# eyes.net
KiCad netlist of a schematic drawn in EAGLE
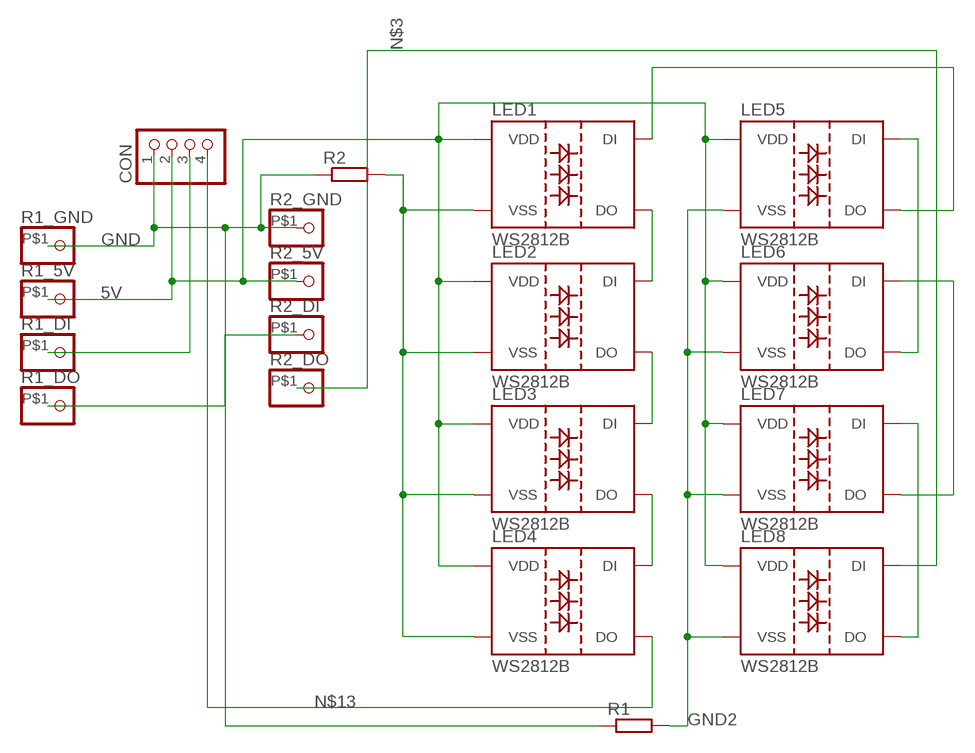
[diagram p0: schematic, sheet 1]

(export (version "E")
  (design (tool "Eeschema 10.0.6"))
  (components
    (comp (ref "CON")
      (value "PINHD-1X4")
      (footprint "eagle-import:1X04")
      (libsource (lib "eagle-import") (part "PINHD-1X4"))
    )
    (comp (ref "LED1")
      (value "WS2812B")
      (footprint "eagle-import:WS2812B")
      (libsource (lib "eagle-import") (part "WS2812B"))
    )
    (comp (ref "LED2")
      (value "WS2812B")
      (footprint "eagle-import:WS2812B")
      (libsource (lib "eagle-import") (part "WS2812B"))
    )
    (comp (ref "LED3")
      (value "WS2812B")
      (footprint "eagle-import:WS2812B")
      (libsource (lib "eagle-import") (part "WS2812B"))
    )
    (comp (ref "LED4")
      (value "WS2812B")
      (footprint "eagle-import:WS2812B")
      (libsource (lib "eagle-import") (part "WS2812B"))
    )
    (comp (ref "LED5")
      (value "WS2812B")
      (footprint "eagle-import:WS2812B")
      (libsource (lib "eagle-import") (part "WS2812B"))
    )
    (comp (ref "LED6")
      (value "WS2812B")
      (footprint "eagle-import:WS2812B")
      (libsource (lib "eagle-import") (part "WS2812B"))
    )
    (comp (ref "LED7")
      (value "WS2812B")
      (footprint "eagle-import:WS2812B")
      (libsource (lib "eagle-import") (part "WS2812B"))
    )
    (comp (ref "LED8")
      (value "WS2812B")
      (footprint "eagle-import:WS2812B")
      (libsource (lib "eagle-import") (part "WS2812B"))
    )
    (comp (ref "R1")
      (value "R-EU_0207/7")
      (footprint "eagle-import:0207_7")
      (libsource (lib "eagle-import") (part "R-EU_0207/7"))
    )
    (comp (ref "R1_5V")
      (value "PINHD-1X1-BIGPOGO")
      (footprint "eagle-import:1X1-BIGPOGO")
      (libsource (lib "eagle-import") (part "PINHD-1X1-BIGPOGO"))
    )
    (comp (ref "R1_DI")
      (value "PINHD-1X1-BIGPOGO")
      (footprint "eagle-import:1X1-BIGPOGO")
      (libsource (lib "eagle-import") (part "PINHD-1X1-BIGPOGO"))
    )
    (comp (ref "R1_DO")
      (value "PINHD-1X1-BIGPOGO")
      (footprint "eagle-import:1X1-BIGPOGO")
      (libsource (lib "eagle-import") (part "PINHD-1X1-BIGPOGO"))
    )
    (comp (ref "R1_GND")
      (value "PINHD-1X1-BIGPOGO")
      (footprint "eagle-import:1X1-BIGPOGO")
      (libsource (lib "eagle-import") (part "PINHD-1X1-BIGPOGO"))
    )
    (comp (ref "R2")
      (value "R-EU_0207/7")
      (footprint "eagle-import:0207_7")
      (libsource (lib "eagle-import") (part "R-EU_0207/7"))
    )
    (comp (ref "R2_5V")
      (value "PINHD-1X1-BIGPOGO")
      (footprint "eagle-import:1X1-BIGPOGO")
      (libsource (lib "eagle-import") (part "PINHD-1X1-BIGPOGO"))
    )
    (comp (ref "R2_DI")
      (value "PINHD-1X1-BIGPOGO")
      (footprint "eagle-import:1X1-BIGPOGO")
      (libsource (lib "eagle-import") (part "PINHD-1X1-BIGPOGO"))
    )
    (comp (ref "R2_DO")
      (value "PINHD-1X1-BIGPOGO")
      (footprint "eagle-import:1X1-BIGPOGO")
      (libsource (lib "eagle-import") (part "PINHD-1X1-BIGPOGO"))
    )
    (comp (ref "R2_GND")
      (value "PINHD-1X1-BIGPOGO")
      (footprint "eagle-import:1X1-BIGPOGO")
      (libsource (lib "eagle-import") (part "PINHD-1X1-BIGPOGO"))
    )
  )
  (nets
    (net (code "1") (name "/5V") (class "Default")
      (node (ref "CON") (pin "2") (pinfunction "2_2") (pintype "passive"))
      (node (ref "LED1") (pin "1") (pinfunction "VDD_1") (pintype "bidirectional"))
      (node (ref "LED2") (pin "1") (pinfunction "VDD_1") (pintype "bidirectional"))
      (node (ref "LED3") (pin "1") (pinfunction "VDD_1") (pintype "bidirectional"))
      (node (ref "LED4") (pin "1") (pinfunction "VDD_1") (pintype "bidirectional"))
      (node (ref "LED5") (pin "1") (pinfunction "VDD_1") (pintype "bidirectional"))
      (node (ref "LED6") (pin "1") (pinfunction "VDD_1") (pintype "bidirectional"))
      (node (ref "LED7") (pin "1") (pinfunction "VDD_1") (pintype "bidirectional"))
      (node (ref "LED8") (pin "1") (pinfunction "VDD_1") (pintype "bidirectional"))
      (node (ref "R1_5V") (pin "P$1") (pinfunction "1_P$1") (pintype "passive"))
      (node (ref "R2_5V") (pin "P$1") (pinfunction "1_P$1") (pintype "passive"))
    )
    (net (code "2") (name "/GND") (class "Default")
      (node (ref "CON") (pin "1") (pinfunction "1_1") (pintype "passive"))
      (node (ref "R1") (pin "1") (pinfunction "1_1") (pintype "passive"))
      (node (ref "R1_GND") (pin "P$1") (pinfunction "1_P$1") (pintype "passive"))
      (node (ref "R2") (pin "1") (pinfunction "1_1") (pintype "passive"))
      (node (ref "R2_GND") (pin "P$1") (pinfunction "1_P$1") (pintype "passive"))
    )
    (net (code "3") (name "/GND2") (class "Default")
      (node (ref "LED5") (pin "3") (pinfunction "VSS_3") (pintype "bidirectional"))
      (node (ref "LED6") (pin "3") (pinfunction "VSS_3") (pintype "bidirectional"))
      (node (ref "LED7") (pin "3") (pinfunction "VSS_3") (pintype "bidirectional"))
      (node (ref "LED8") (pin "3") (pinfunction "VSS_3") (pintype "bidirectional"))
      (node (ref "R1") (pin "2") (pinfunction "2_2") (pintype "passive"))
    )
    (net (code "4") (name "/N$3") (class "Default")
      (node (ref "LED8") (pin "4") (pinfunction "DI_4") (pintype "bidirectional"))
      (node (ref "R2_DO") (pin "P$1") (pinfunction "1_P$1") (pintype "passive"))
    )
    (net (code "5") (name "/N$13") (class "Default")
      (node (ref "CON") (pin "4") (pinfunction "4_4") (pintype "passive"))
      (node (ref "LED4") (pin "2") (pinfunction "DO_2") (pintype "bidirectional"))
    )
    (net (code "6") (name "Net-(LED1-DI)") (class "Default")
      (node (ref "LED1") (pin "4") (pinfunction "DI_4") (pintype "bidirectional"))
      (node (ref "LED5") (pin "2") (pinfunction "DO_2") (pintype "bidirectional"))
    )
    (net (code "7") (name "Net-(LED1-DO)") (class "Default")
      (node (ref "LED1") (pin "2") (pinfunction "DO_2") (pintype "bidirectional"))
      (node (ref "LED2") (pin "4") (pinfunction "DI_4") (pintype "bidirectional"))
    )
    (net (code "8") (name "Net-(LED1-VSS)") (class "Default")
      (node (ref "LED1") (pin "3") (pinfunction "VSS_3") (pintype "bidirectional"))
      (node (ref "LED2") (pin "3") (pinfunction "VSS_3") (pintype "bidirectional"))
      (node (ref "LED3") (pin "3") (pinfunction "VSS_3") (pintype "bidirectional"))
      (node (ref "LED4") (pin "3") (pinfunction "VSS_3") (pintype "bidirectional"))
      (node (ref "R2") (pin "2") (pinfunction "2_2") (pintype "passive"))
    )
    (net (code "9") (name "Net-(LED2-DO)") (class "Default")
      (node (ref "LED2") (pin "2") (pinfunction "DO_2") (pintype "bidirectional"))
      (node (ref "LED3") (pin "4") (pinfunction "DI_4") (pintype "bidirectional"))
    )
    (net (code "10") (name "Net-(LED3-DO)") (class "Default")
      (node (ref "LED3") (pin "2") (pinfunction "DO_2") (pintype "bidirectional"))
      (node (ref "LED4") (pin "4") (pinfunction "DI_4") (pintype "bidirectional"))
    )
    (net (code "11") (name "Net-(LED5-DI)") (class "Default")
      (node (ref "LED5") (pin "4") (pinfunction "DI_4") (pintype "bidirectional"))
      (node (ref "LED6") (pin "2") (pinfunction "DO_2") (pintype "bidirectional"))
    )
    (net (code "12") (name "Net-(LED6-DI)") (class "Default")
      (node (ref "LED6") (pin "4") (pinfunction "DI_4") (pintype "bidirectional"))
      (node (ref "LED7") (pin "2") (pinfunction "DO_2") (pintype "bidirectional"))
    )
    (net (code "13") (name "Net-(LED7-DI)") (class "Default")
      (node (ref "LED7") (pin "4") (pinfunction "DI_4") (pintype "bidirectional"))
      (node (ref "LED8") (pin "2") (pinfunction "DO_2") (pintype "bidirectional"))
    )
    (net (code "14") (name "Net-(R1_DI-1)") (class "Default")
      (node (ref "CON") (pin "3") (pinfunction "3_3") (pintype "passive"))
      (node (ref "R1_DI") (pin "P$1") (pinfunction "1_P$1") (pintype "passive"))
    )
    (net (code "15") (name "Net-(R1_DO-1)") (class "Default")
      (node (ref "R1_DO") (pin "P$1") (pinfunction "1_P$1") (pintype "passive"))
      (node (ref "R2_DI") (pin "P$1") (pinfunction "1_P$1") (pintype "passive"))
    )
  )
)
